# CONNECTORS.net
KiCad netlist of a schematic drawn in Altium Designer
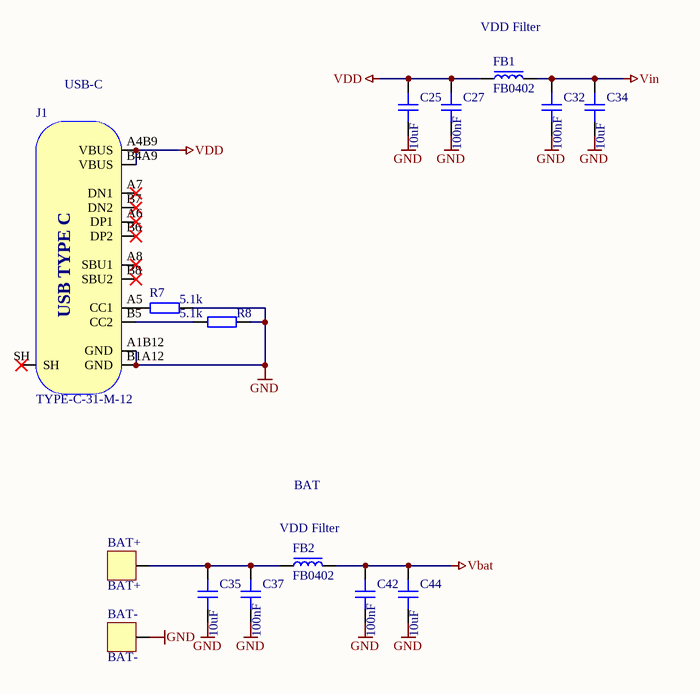
[diagram p0: CONNECTORS.SchDoc]

(export (version "E")
  (design (tool "Eeschema 10.0.6"))
  (components
    (comp (ref "BAT+")
      (value "BAT+")
      (footprint "PAD_SQ_2MM")
      (description "Test Point Square 2mm")
      (libsource (lib "Schematic-Lib-PhilsLab") (part "PAD_SQ_2MM"))
    )
    (comp (ref "BAT-")
      (value "BAT-")
      (footprint "PAD_SQ_2MM")
      (description "Test Point Square 2mm")
      (libsource (lib "Schematic-Lib-PhilsLab") (part "PAD_SQ_2MM"))
    )
    (comp (ref "C25")
      (value "10uF")
      (footprint "CAP_0402")
      (description "Capacitor SMD 0402 10V")
      (fields (field (name "Comment") "C0402_10V"))
      (libsource (lib "Schematic-Lib-PhilsLab") (part "CAP_0402_10V"))
    )
    (comp (ref "C27")
      (value "100nF")
      (footprint "CAP_0402")
      (description "Capacitor SMD 0402 10V")
      (fields (field (name "Comment") "C0402_10V"))
      (libsource (lib "Schematic-Lib-PhilsLab") (part "CAP_0402_10V"))
    )
    (comp (ref "C32")
      (value "100nF")
      (footprint "CAP_0402")
      (description "Capacitor SMD 0402 10V")
      (fields (field (name "Comment") "C0402_10V"))
      (libsource (lib "Schematic-Lib-PhilsLab") (part "CAP_0402_10V"))
    )
    (comp (ref "C34")
      (value "10uF")
      (footprint "CAP_0402")
      (description "Capacitor SMD 0402 10V")
      (fields (field (name "Comment") "C0402_10V"))
      (libsource (lib "Schematic-Lib-PhilsLab") (part "CAP_0402_10V"))
    )
    (comp (ref "C35")
      (value "10uF")
      (footprint "CAP_0402")
      (description "Capacitor SMD 0402 10V")
      (fields (field (name "Comment") "C0402_10V"))
      (libsource (lib "Schematic-Lib-PhilsLab") (part "CAP_0402_10V"))
    )
    (comp (ref "C37")
      (value "100nF")
      (footprint "CAP_0402")
      (description "Capacitor SMD 0402 10V")
      (fields (field (name "Comment") "C0402_10V"))
      (libsource (lib "Schematic-Lib-PhilsLab") (part "CAP_0402_10V"))
    )
    (comp (ref "C42")
      (value "100nF")
      (footprint "CAP_0402")
      (description "Capacitor SMD 0402 10V")
      (fields (field (name "Comment") "C0402_10V"))
      (libsource (lib "Schematic-Lib-PhilsLab") (part "CAP_0402_10V"))
    )
    (comp (ref "C44")
      (value "10uF")
      (footprint "CAP_0402")
      (description "Capacitor SMD 0402 10V")
      (fields (field (name "Comment") "C0402_10V"))
      (libsource (lib "Schematic-Lib-PhilsLab") (part "CAP_0402_10V"))
    )
    (comp (ref "FB1")
      (value "FB0402")
      (footprint "FB_0402")
      (description "Ferrite Bead SMD 0402")
      (libsource (lib "Schematic-Lib-PhilsLab") (part "FB_0402"))
    )
    (comp (ref "FB2")
      (value "FB0402")
      (footprint "FB_0402")
      (description "Ferrite Bead SMD 0402")
      (libsource (lib "Schematic-Lib-PhilsLab") (part "FB_0402"))
    )
    (comp (ref "J1")
      (value "TYPE-C-31-M-12")
      (footprint "TYPE-C-31-M-12")
      (description "USB Type C Connector Horizontal SMT")
      (fields (field (name "MANUFACTURER") "Koren Hroparts"))
      (libsource (lib "Schematic-Lib-PhilsLab") (part "TYPE-C-31-M-12"))
    )
    (comp (ref "R7")
      (value "5.1k")
      (footprint "RES_0402")
      (description "Resistor SMD 0402")
      (fields (field (name "Comment") "R0402"))
      (libsource (lib "Schematic-Lib-PhilsLab") (part "RES_0402"))
    )
    (comp (ref "R8")
      (value "5.1k")
      (footprint "RES_0402")
      (description "Resistor SMD 0402")
      (fields (field (name "Comment") "R0402"))
      (libsource (lib "Schematic-Lib-PhilsLab") (part "RES_0402"))
    )
  )
  (nets
    (net (code "1") (name "GND") (class "Default")
      (node (ref "BAT-") (pin "1") (pinfunction "1_1") (pintype "passive"))
      (node (ref "C25") (pin "1") (pinfunction "1_1") (pintype "passive"))
      (node (ref "C27") (pin "1") (pinfunction "1_1") (pintype "passive"))
      (node (ref "C32") (pin "1") (pinfunction "1_1") (pintype "passive"))
      (node (ref "C34") (pin "1") (pinfunction "1_1") (pintype "passive"))
      (node (ref "C35") (pin "1") (pinfunction "1_1") (pintype "passive"))
      (node (ref "C37") (pin "1") (pinfunction "1_1") (pintype "passive"))
      (node (ref "C42") (pin "1") (pinfunction "1_1") (pintype "passive"))
      (node (ref "C44") (pin "1") (pinfunction "1_1") (pintype "passive"))
      (node (ref "J1") (pin "A1B12") (pinfunction "GND_A1B12") (pintype "power_in"))
      (node (ref "J1") (pin "B1A12") (pinfunction "GND_B1A12") (pintype "power_in"))
      (node (ref "R7") (pin "2") (pinfunction "2_2") (pintype "passive"))
      (node (ref "R8") (pin "2") (pinfunction "2_2") (pintype "passive"))
    )
    (net (code "2") (name "Net-(BAT+-Pad1)") (class "Default")
      (node (ref "BAT+") (pin "1") (pinfunction "1_1") (pintype "passive"))
      (node (ref "C35") (pin "2") (pinfunction "2_2") (pintype "passive"))
      (node (ref "C37") (pin "2") (pinfunction "2_2") (pintype "passive"))
      (node (ref "FB2") (pin "1") (pinfunction "1_1") (pintype "passive"))
    )
    (net (code "3") (name "Net-(J1-CC1)") (class "Default")
      (node (ref "J1") (pin "A5") (pinfunction "CC1_A5") (pintype "passive"))
      (node (ref "R7") (pin "1") (pinfunction "1_1") (pintype "passive"))
    )
    (net (code "4") (name "Net-(J1-CC2)") (class "Default")
      (node (ref "J1") (pin "B5") (pinfunction "CC2_B5") (pintype "tri_state"))
      (node (ref "R8") (pin "1") (pinfunction "1_1") (pintype "passive"))
    )
    (net (code "5") (name "VDD") (class "Default")
      (node (ref "C25") (pin "2") (pinfunction "2_2") (pintype "passive"))
      (node (ref "C27") (pin "2") (pinfunction "2_2") (pintype "passive"))
      (node (ref "FB1") (pin "1") (pinfunction "1_1") (pintype "passive"))
      (node (ref "J1") (pin "A4B9") (pinfunction "VBUS_A4B9") (pintype "power_in"))
      (node (ref "J1") (pin "B4A9") (pinfunction "VBUS_B4A9") (pintype "power_in"))
    )
    (net (code "6") (name "Vbat") (class "Default")
      (node (ref "C42") (pin "2") (pinfunction "2_2") (pintype "passive"))
      (node (ref "C44") (pin "2") (pinfunction "2_2") (pintype "passive"))
      (node (ref "FB2") (pin "2") (pinfunction "2_2") (pintype "passive"))
    )
    (net (code "7") (name "Vin") (class "Default")
      (node (ref "C32") (pin "2") (pinfunction "2_2") (pintype "passive"))
      (node (ref "C34") (pin "2") (pinfunction "2_2") (pintype "passive"))
      (node (ref "FB1") (pin "2") (pinfunction "2_2") (pintype "passive"))
    )
    (net (code "8") (name "unconnected-(J1-DN1-PadA7)") (class "Default")
      (node (ref "J1") (pin "A7") (pinfunction "DN1_A7") (pintype "bidirectional+no_connect"))
    )
    (net (code "9") (name "unconnected-(J1-DN2-PadB7)") (class "Default")
      (node (ref "J1") (pin "B7") (pinfunction "DN2_B7") (pintype "bidirectional+no_connect"))
    )
    (net (code "10") (name "unconnected-(J1-DP1-PadA6)") (class "Default")
      (node (ref "J1") (pin "A6") (pinfunction "DP1_A6") (pintype "bidirectional+no_connect"))
    )
    (net (code "11") (name "unconnected-(J1-DP2-PadB6)") (class "Default")
      (node (ref "J1") (pin "B6") (pinfunction "DP2_B6") (pintype "bidirectional+no_connect"))
    )
    (net (code "12") (name "unconnected-(J1-PadSH)") (class "Default")
      (node (ref "J1") (pin "SH") (pinfunction "SH_SH") (pintype "power_in+no_connect"))
    )
    (net (code "13") (name "unconnected-(J1-SBU1-PadA8)") (class "Default")
      (node (ref "J1") (pin "A8") (pinfunction "SBU1_A8") (pintype "bidirectional+no_connect"))
    )
    (net (code "14") (name "unconnected-(J1-SBU2-PadB8)") (class "Default")
      (node (ref "J1") (pin "B8") (pinfunction "SBU2_B8") (pintype "bidirectional+no_connect"))
    )
  )
)
